# NRF24L01.net
KiCad netlist of a schematic drawn in Altium Designer
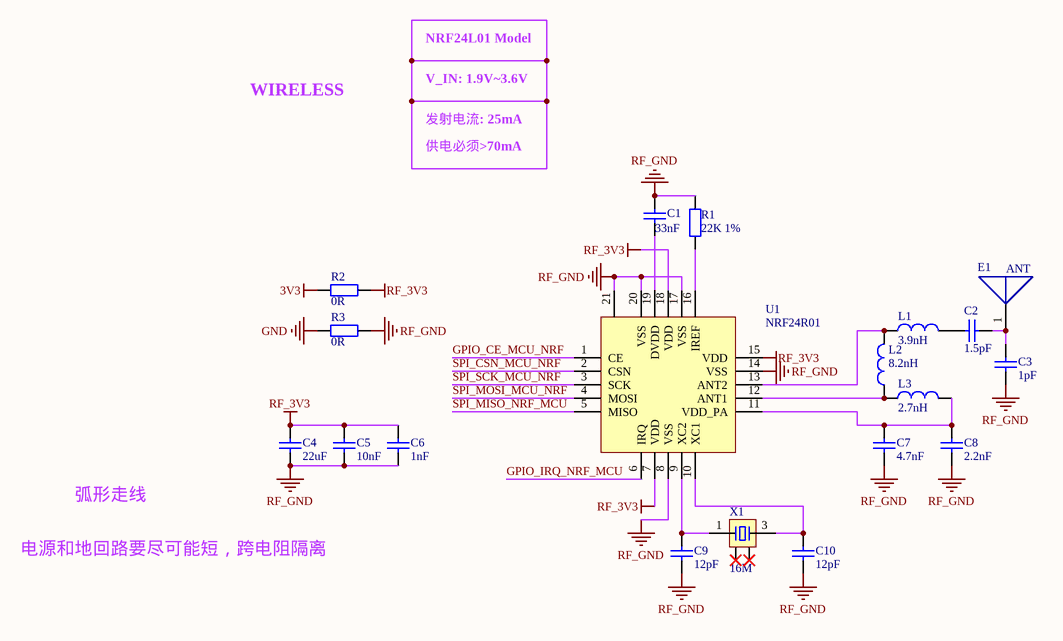
[diagram p0: NRF24L01.SchDoc]

(export (version "E")
  (design (tool "Eeschema 10.0.6"))
  (components
    (comp (ref "C1")
      (value "33nF")
      (footprint "Cap-0603")
      (description "贴片陶瓷电容")
      (libsource (lib "Miscellaneous Base") (part "CAP"))
    )
    (comp (ref "C2")
      (value "1.5pF")
      (footprint "Cap-0402")
      (description "贴片陶瓷电容")
      (libsource (lib "Miscellaneous Base") (part "CAP"))
    )
    (comp (ref "C3")
      (value "1pF")
      (footprint "Cap-0402")
      (description "贴片陶瓷电容")
      (libsource (lib "Miscellaneous Base") (part "CAP"))
    )
    (comp (ref "C4")
      (value "22uF")
      (footprint "Cap-0805")
      (description "贴片陶瓷电容")
      (libsource (lib "Miscellaneous Base") (part "CAP"))
    )
    (comp (ref "C5")
      (value "10nF")
      (footprint "Cap-0603")
      (description "贴片陶瓷电容")
      (libsource (lib "Miscellaneous Base") (part "CAP"))
    )
    (comp (ref "C6")
      (value "1nF")
      (footprint "Cap-0603")
      (description "贴片陶瓷电容")
      (libsource (lib "Miscellaneous Base") (part "CAP"))
    )
    (comp (ref "C7")
      (value "4.7nF")
      (footprint "Cap-0402")
      (description "贴片陶瓷电容")
      (libsource (lib "Miscellaneous Base") (part "CAP"))
    )
    (comp (ref "C8")
      (value "2.2nF")
      (footprint "Cap-0402")
      (description "贴片陶瓷电容")
      (libsource (lib "Miscellaneous Base") (part "CAP"))
    )
    (comp (ref "C9")
      (value "12pF")
      (footprint "Cap-0603")
      (description "贴片陶瓷电容")
      (libsource (lib "Miscellaneous Base") (part "CAP"))
    )
    (comp (ref "C10")
      (value "12pF")
      (footprint "Cap-0603")
      (description "贴片陶瓷电容")
      (libsource (lib "Miscellaneous Base") (part "CAP"))
    )
    (comp (ref "E1")
      (value "ANT")
      (footprint "AN2051-245")
      (fields (field (name "PUBLISHER") "mazhongwei"))
      (libsource (lib "Miscellaneous Others") (part "ANT"))
    )
    (comp (ref "L1")
      (value "3.9nH")
      (footprint "L-0402")
      (description "贴片电感")
      (libsource (lib "Miscellaneous Base") (part "INDUCTOR"))
    )
    (comp (ref "L2")
      (value "8.2nH")
      (footprint "L-0402")
      (description "贴片电感")
      (libsource (lib "Miscellaneous Base") (part "INDUCTOR"))
    )
    (comp (ref "L3")
      (value "2.7nH")
      (footprint "L-0402")
      (description "贴片电感")
      (libsource (lib "Miscellaneous Base") (part "INDUCTOR"))
    )
    (comp (ref "R1")
      (value "22K 1%")
      (footprint "Res-0603")
      (description "贴片电阻")
      (libsource (lib "Miscellaneous Base") (part "RES"))
    )
    (comp (ref "R2")
      (value "0R")
      (footprint "Res-0603")
      (description "贴片电阻")
      (libsource (lib "") (part "RES_1"))
    )
    (comp (ref "R3")
      (value "0R")
      (footprint "Res-0603")
      (description "贴片电阻")
      (libsource (lib "") (part "RES_1"))
    )
    (comp (ref "U1")
      (value "NRF24R01")
      (footprint "QFN20 4x4")
      (description "2.4G无线")
      (libsource (lib "Miscellaneous IC") (part "NRF24R01"))
    )
    (comp (ref "X1")
      (value "16M")
      (footprint "OSC 3225-4P")
      (description "4脚无源晶振")
      (libsource (lib "Miscellaneous XTAL") (part "XTAL-4P"))
    )
  )
  (nets
    (net (code "1") (name "/GPIO_CE_MCU_NRF") (class "Default")
      (node (ref "U1") (pin "1") (pinfunction "CE_1") (pintype "passive"))
    )
    (net (code "2") (name "/GPIO_IRQ_NRF_MCU") (class "Default")
      (node (ref "U1") (pin "6") (pinfunction "IRQ_6") (pintype "passive"))
    )
    (net (code "3") (name "/SPI_CSN_MCU_NRF") (class "Default")
      (node (ref "U1") (pin "2") (pinfunction "CSN_2") (pintype "passive"))
    )
    (net (code "4") (name "/SPI_MISO_NRF_MCU") (class "Default")
      (node (ref "U1") (pin "5") (pinfunction "MISO_5") (pintype "passive"))
    )
    (net (code "5") (name "/SPI_MOSI_MCU_NRF") (class "Default")
      (node (ref "U1") (pin "4") (pinfunction "MOSI_4") (pintype "passive"))
    )
    (net (code "6") (name "/SPI_SCK_MCU_NRF") (class "Default")
      (node (ref "U1") (pin "3") (pinfunction "SCK_3") (pintype "passive"))
    )
    (net (code "7") (name "3V3") (class "Default")
      (node (ref "R2") (pin "1") (pinfunction "1_1") (pintype "passive"))
    )
    (net (code "8") (name "GND") (class "Default")
      (node (ref "R3") (pin "1") (pinfunction "1_1") (pintype "passive"))
    )
    (net (code "9") (name "Net-(C2-Pad1)") (class "Default")
      (node (ref "C2") (pin "1") (pinfunction "1_1") (pintype "passive"))
      (node (ref "L1") (pin "2") (pinfunction "2_2") (pintype "passive"))
    )
    (net (code "10") (name "Net-(C2-Pad2)") (class "Default")
      (node (ref "C2") (pin "2") (pinfunction "2_2") (pintype "passive"))
      (node (ref "C3") (pin "2") (pinfunction "2_2") (pintype "passive"))
      (node (ref "E1") (pin "1") (pinfunction "1_1") (pintype "passive"))
    )
    (net (code "11") (name "Net-(U1-ANT1)") (class "Default")
      (node (ref "L2") (pin "1") (pinfunction "1_1") (pintype "passive"))
      (node (ref "L3") (pin "1") (pinfunction "1_1") (pintype "passive"))
      (node (ref "U1") (pin "12") (pinfunction "ANT1_12") (pintype "passive"))
    )
    (net (code "12") (name "Net-(U1-ANT2)") (class "Default")
      (node (ref "L1") (pin "1") (pinfunction "1_1") (pintype "passive"))
      (node (ref "L2") (pin "2") (pinfunction "2_2") (pintype "passive"))
      (node (ref "U1") (pin "13") (pinfunction "ANT2_13") (pintype "passive"))
    )
    (net (code "13") (name "Net-(U1-DVDD)") (class "Default")
      (node (ref "C1") (pin "2") (pinfunction "2_2") (pintype "passive"))
      (node (ref "U1") (pin "19") (pinfunction "DVDD_19") (pintype "passive"))
    )
    (net (code "14") (name "Net-(U1-IREF)") (class "Default")
      (node (ref "R1") (pin "2") (pinfunction "2_2") (pintype "passive"))
      (node (ref "U1") (pin "16") (pinfunction "IREF_16") (pintype "passive"))
    )
    (net (code "15") (name "Net-(U1-VDD_PA)") (class "Default")
      (node (ref "C7") (pin "2") (pinfunction "2_2") (pintype "passive"))
      (node (ref "C8") (pin "2") (pinfunction "2_2") (pintype "passive"))
      (node (ref "L3") (pin "2") (pinfunction "2_2") (pintype "passive"))
      (node (ref "U1") (pin "11") (pinfunction "VDD_PA_11") (pintype "passive"))
    )
    (net (code "16") (name "Net-(U1-XC1)") (class "Default")
      (node (ref "C10") (pin "2") (pinfunction "2_2") (pintype "passive"))
      (node (ref "U1") (pin "10") (pinfunction "XC1_10") (pintype "passive"))
      (node (ref "X1") (pin "3") (pinfunction "3_3") (pintype "passive"))
    )
    (net (code "17") (name "Net-(U1-XC2)") (class "Default")
      (node (ref "C9") (pin "2") (pinfunction "2_2") (pintype "passive"))
      (node (ref "U1") (pin "9") (pinfunction "XC2_9") (pintype "passive"))
      (node (ref "X1") (pin "1") (pinfunction "1_1") (pintype "passive"))
    )
    (net (code "18") (name "RF_3V3") (class "Default")
      (node (ref "C4") (pin "1") (pinfunction "1_1") (pintype "passive"))
      (node (ref "C5") (pin "2") (pinfunction "2_2") (pintype "passive"))
      (node (ref "C6") (pin "2") (pinfunction "2_2") (pintype "passive"))
      (node (ref "R2") (pin "2") (pinfunction "2_2") (pintype "passive"))
      (node (ref "U1") (pin "15") (pinfunction "VDD_15") (pintype "passive"))
      (node (ref "U1") (pin "18") (pinfunction "VDD_18") (pintype "passive"))
      (node (ref "U1") (pin "7") (pinfunction "VDD_7") (pintype "passive"))
    )
    (net (code "19") (name "RF_GND") (class "Default")
      (node (ref "C1") (pin "1") (pinfunction "1_1") (pintype "passive"))
      (node (ref "C10") (pin "1") (pinfunction "1_1") (pintype "passive"))
      (node (ref "C3") (pin "1") (pinfunction "1_1") (pintype "passive"))
      (node (ref "C4") (pin "2") (pinfunction "2_2") (pintype "passive"))
      (node (ref "C5") (pin "1") (pinfunction "1_1") (pintype "passive"))
      (node (ref "C6") (pin "1") (pinfunction "1_1") (pintype "passive"))
      (node (ref "C7") (pin "1") (pinfunction "1_1") (pintype "passive"))
      (node (ref "C8") (pin "1") (pinfunction "1_1") (pintype "passive"))
      (node (ref "C9") (pin "1") (pinfunction "1_1") (pintype "passive"))
      (node (ref "R1") (pin "1") (pinfunction "1_1") (pintype "passive"))
      (node (ref "R3") (pin "2") (pinfunction "2_2") (pintype "passive"))
      (node (ref "U1") (pin "14") (pinfunction "VSS_14") (pintype "passive"))
      (node (ref "U1") (pin "17") (pinfunction "VSS_17") (pintype "passive"))
      (node (ref "U1") (pin "20") (pinfunction "VSS_20") (pintype "passive"))
      (node (ref "U1") (pin "21") (pintype "passive"))
      (node (ref "U1") (pin "8") (pinfunction "VSS_8") (pintype "passive"))
    )
    (net (code "20") (name "unconnected-(X1-Pad2)") (class "Default")
      (node (ref "X1") (pin "2") (pinfunction "2_2") (pintype "passive+no_connect"))
    )
    (net (code "21") (name "unconnected-(X1-Pad4)") (class "Default")
      (node (ref "X1") (pin "4") (pinfunction "4_4") (pintype "passive+no_connect"))
    )
  )
)
